# XTXBoard_2CPU.net
KiCad netlist of a schematic drawn in Altium Designer
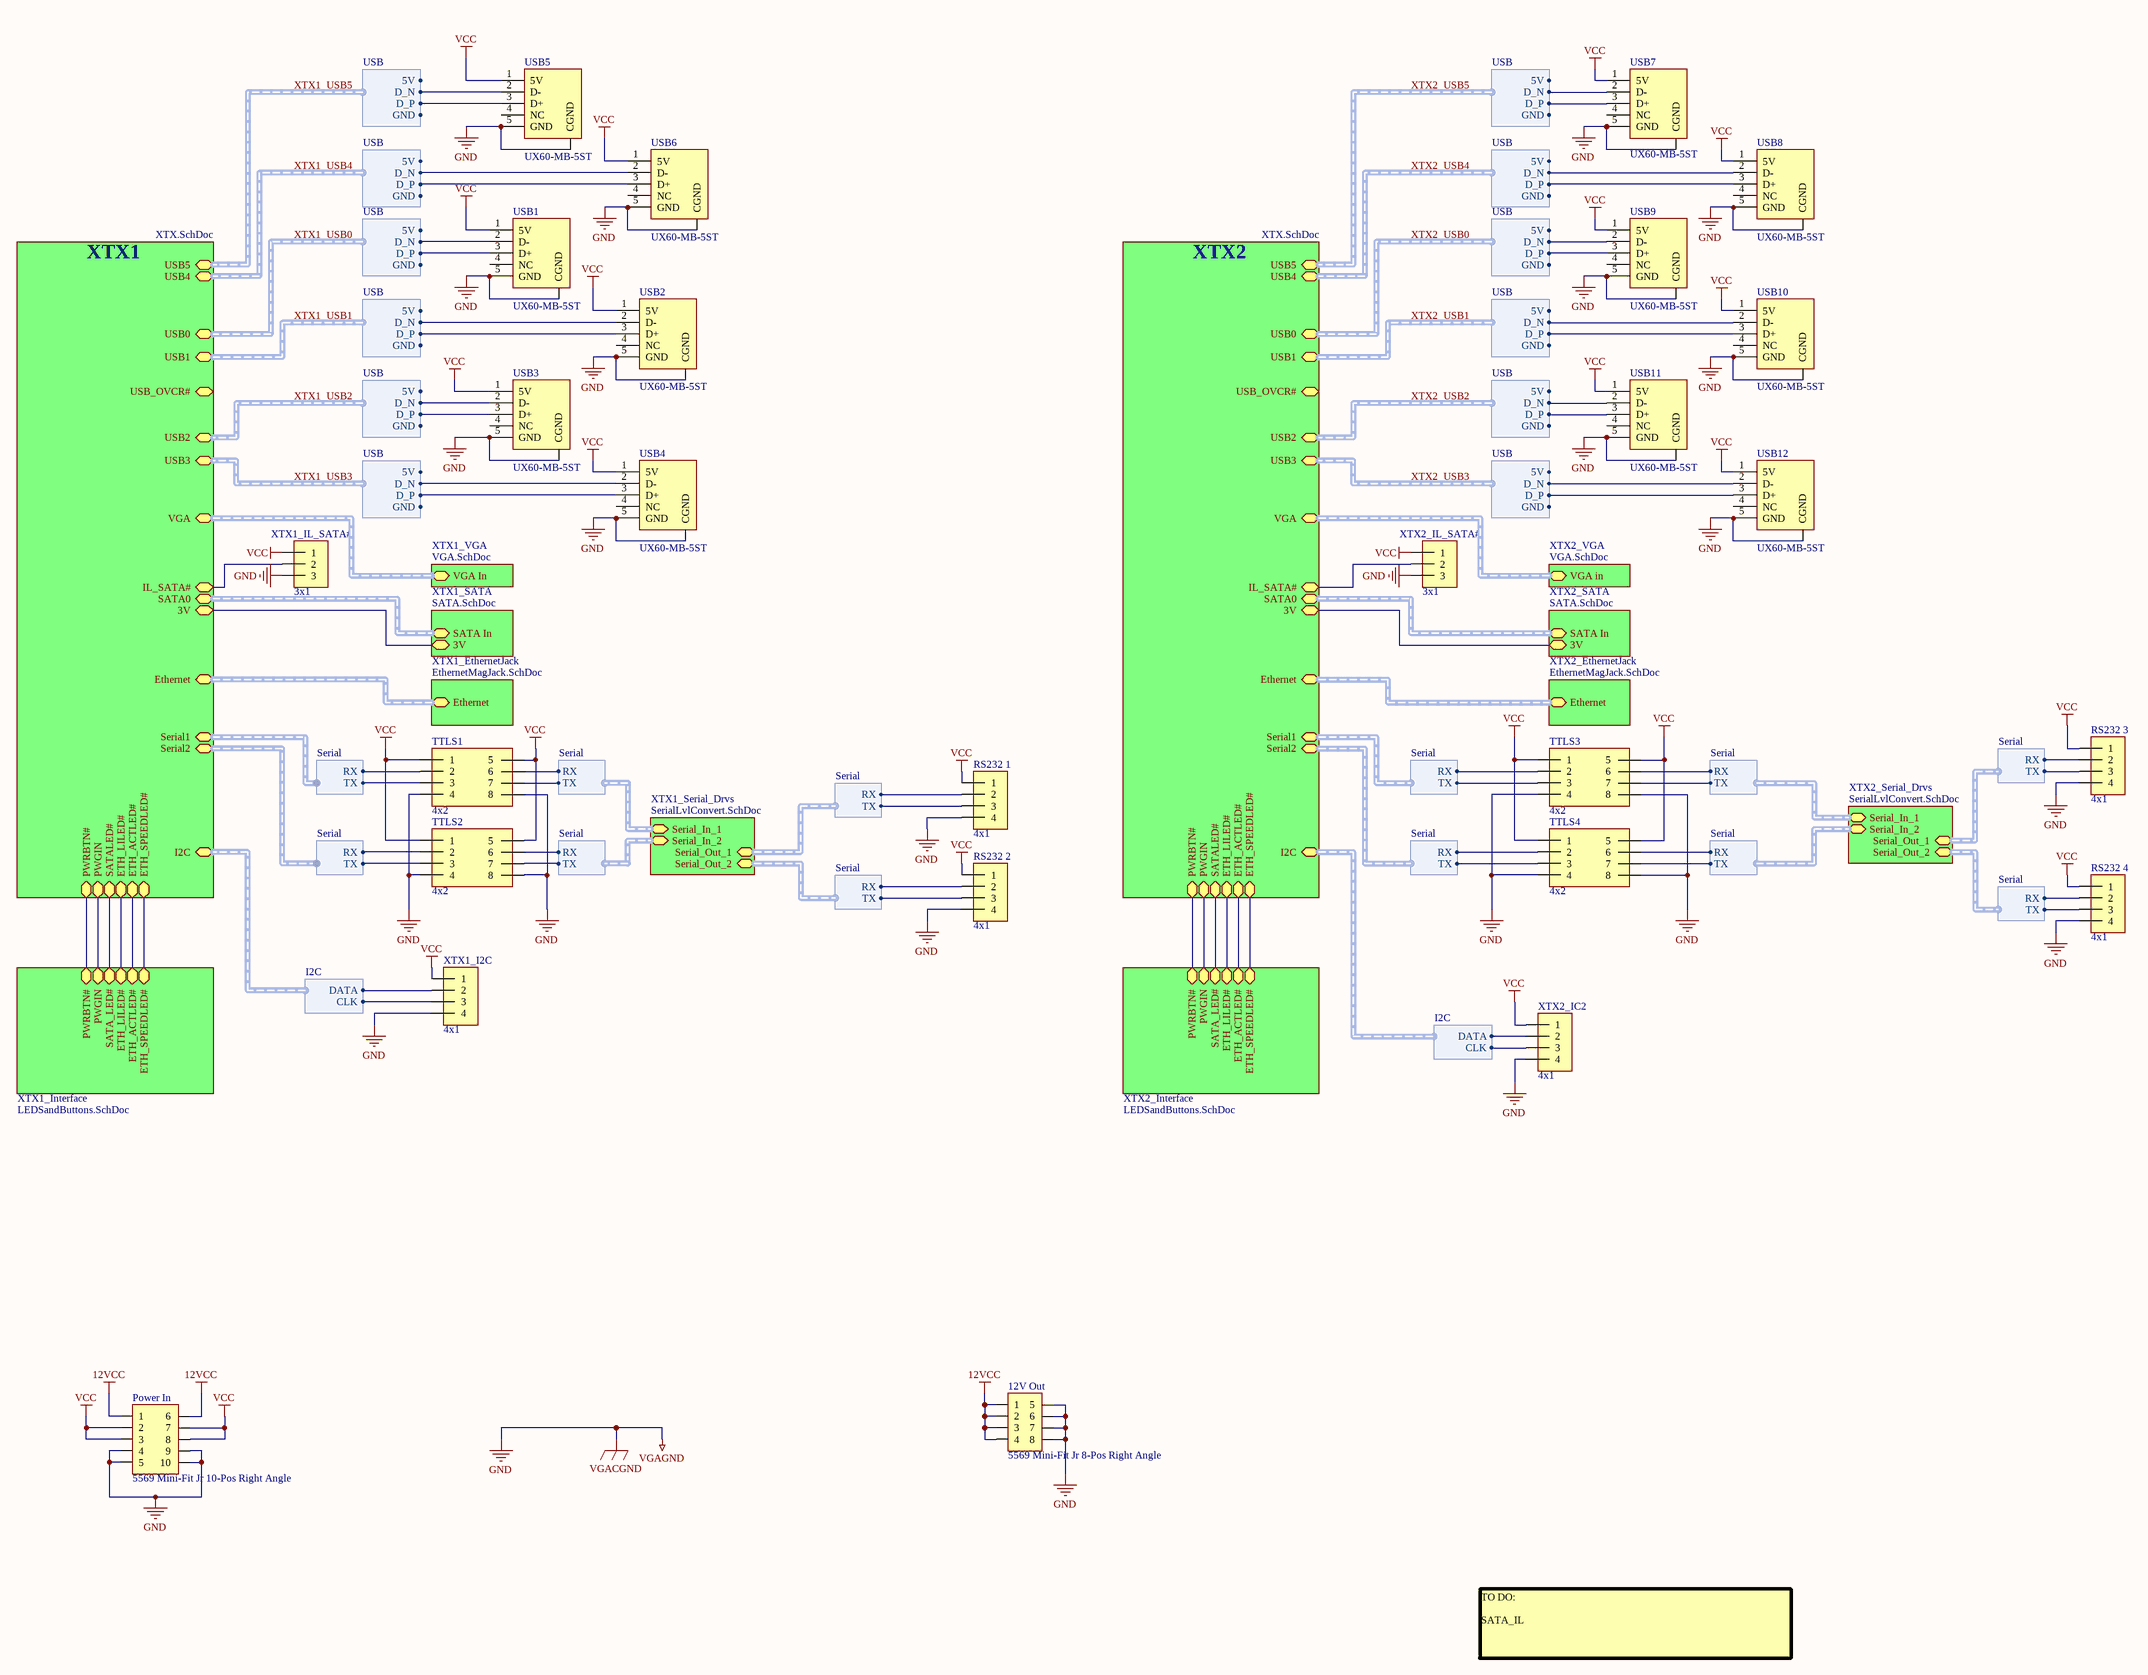
[diagram p0: XTXBoard(2CPU).SchDoc]

(export (version "E")
  (design (tool "Eeschema 10.0.6"))
  (components
    (comp (ref "12V Out")
      (value "5569 Mini-Fit Jr 8-Pos Right Angle")
      (footprint "MolexConnectors:8-POS 5569 Mini-Fit Jr 2")
      (libsource (lib "Molex") (part "5569 Mini-Fit Jr 8-Pos Right Angle"))
    )
    (comp (ref "Power In")
      (value "5569 Mini-Fit Jr 10-Pos Right Angle")
      (footprint "MolexConnectors:10-Pos 5569 Mini-Fit Jr 2")
      (libsource (lib "Molex") (part "5569 Mini-Fit Jr 10-Pos Right Angle"))
    )
    (comp (ref "RS232 1")
      (value "4x1")
      (footprint "Headers:Male 4x1")
      (description "4x1 100mil Header")
      (libsource (lib "Headers") (part "4x1"))
    )
    (comp (ref "RS232 2")
      (value "4x1")
      (footprint "Headers:Male 4x1")
      (description "4x1 100mil Header")
      (libsource (lib "Headers") (part "4x1"))
    )
    (comp (ref "RS232 3")
      (value "4x1")
      (footprint "Headers:Male 4x1")
      (description "4x1 100mil Header")
      (libsource (lib "Headers") (part "4x1"))
    )
    (comp (ref "RS232 4")
      (value "4x1")
      (footprint "Headers:Male 4x1")
      (description "4x1 100mil Header")
      (libsource (lib "Headers") (part "4x1"))
    )
    (comp (ref "TTLS1")
      (value "4x2")
      (footprint "Headers:Male 4x2")
      (description "4x2 100mil Header")
      (libsource (lib "Headers") (part "4x2"))
    )
    (comp (ref "TTLS2")
      (value "4x2")
      (footprint "Headers:Male 4x2")
      (description "4x2 100mil Header")
      (libsource (lib "Headers") (part "4x2"))
    )
    (comp (ref "TTLS3")
      (value "4x2")
      (footprint "Headers:FEMALE 4x2")
      (description "4x2 100mil Header")
      (libsource (lib "Headers") (part "4x2"))
    )
    (comp (ref "TTLS4")
      (value "4x2")
      (footprint "Headers:FEMALE 4x2")
      (description "4x2 100mil Header")
      (libsource (lib "Headers") (part "4x2"))
    )
    (comp (ref "USB1")
      (value "UX60-MB-5ST")
      (footprint "Hirose:UX60-MB-5ST")
      (description "miniUSB Type B SMT Connector")
      (libsource (lib "Hirose") (part "UX60-MB-5ST"))
    )
    (comp (ref "USB2")
      (value "UX60-MB-5ST")
      (footprint "Hirose:UX60-MB-5ST")
      (description "miniUSB Type B SMT Connector")
      (libsource (lib "Hirose") (part "UX60-MB-5ST"))
    )
    (comp (ref "USB3")
      (value "UX60-MB-5ST")
      (footprint "Hirose:UX60-MB-5ST")
      (description "miniUSB Type B SMT Connector")
      (libsource (lib "Hirose") (part "UX60-MB-5ST"))
    )
    (comp (ref "USB4")
      (value "UX60-MB-5ST")
      (footprint "Hirose:UX60-MB-5ST")
      (description "miniUSB Type B SMT Connector")
      (libsource (lib "Hirose") (part "UX60-MB-5ST"))
    )
    (comp (ref "USB5")
      (value "UX60-MB-5ST")
      (footprint "Hirose:UX60-MB-5ST")
      (description "miniUSB Type B SMT Connector")
      (libsource (lib "Hirose") (part "UX60-MB-5ST"))
    )
    (comp (ref "USB6")
      (value "UX60-MB-5ST")
      (footprint "Hirose:UX60-MB-5ST")
      (description "miniUSB Type B SMT Connector")
      (libsource (lib "Hirose") (part "UX60-MB-5ST"))
    )
    (comp (ref "USB7")
      (value "UX60-MB-5ST")
      (footprint "Hirose:UX60-MB-5ST")
      (description "miniUSB Type B SMT Connector")
      (libsource (lib "Hirose") (part "UX60-MB-5ST"))
    )
    (comp (ref "USB8")
      (value "UX60-MB-5ST")
      (footprint "Hirose:UX60-MB-5ST")
      (description "miniUSB Type B SMT Connector")
      (libsource (lib "Hirose") (part "UX60-MB-5ST"))
    )
    (comp (ref "USB9")
      (value "UX60-MB-5ST")
      (footprint "Hirose:UX60-MB-5ST")
      (description "miniUSB Type B SMT Connector")
      (libsource (lib "Hirose") (part "UX60-MB-5ST"))
    )
    (comp (ref "USB10")
      (value "UX60-MB-5ST")
      (footprint "Hirose:UX60-MB-5ST")
      (description "miniUSB Type B SMT Connector")
      (libsource (lib "Hirose") (part "UX60-MB-5ST"))
    )
    (comp (ref "USB11")
      (value "UX60-MB-5ST")
      (footprint "Hirose:UX60-MB-5ST")
      (description "miniUSB Type B SMT Connector")
      (libsource (lib "Hirose") (part "UX60-MB-5ST"))
    )
    (comp (ref "USB12")
      (value "UX60-MB-5ST")
      (footprint "Hirose:UX60-MB-5ST")
      (description "miniUSB Type B SMT Connector")
      (libsource (lib "Hirose") (part "UX60-MB-5ST"))
    )
    (comp (ref "XTX1_I2C")
      (value "4x1")
      (footprint "Headers:Male 4x1")
      (description "4x1 100mil Header")
      (libsource (lib "Headers") (part "4x1"))
    )
    (comp (ref "XTX1_IL_SATA#")
      (value "3x1")
      (footprint "Headers:Male 3x1")
      (description "3x1 100mil Header")
      (libsource (lib "Headers") (part "3x1"))
    )
    (comp (ref "XTX2_IC2")
      (value "4x1")
      (footprint "Headers:Male 4x1")
      (description "4x1 100mil Header")
      (libsource (lib "Headers") (part "4x1"))
    )
    (comp (ref "XTX2_IL_SATA#")
      (value "3x1")
      (footprint "Headers:Male 3x1")
      (description "3x1 100mil Header")
      (libsource (lib "Headers") (part "3x1"))
    )
  )
  (nets
    (net (code "25") (name "/IL_SATA#") (class "Default")
      (node (ref "XTX2_IL_SATA#") (pin "2") (pinfunction "2_2") (pintype "passive"))
    )
    (net (code "26") (name "/IL_SATA#_1") (class "Default")
      (node (ref "XTX1_IL_SATA#") (pin "2") (pinfunction "2_2") (pintype "passive"))
    )
    (net (code "53") (name "12VCC") (class "Default")
      (node (ref "12V Out") (pin "1") (pinfunction "1_1") (pintype "passive"))
      (node (ref "12V Out") (pin "2") (pinfunction "2_2") (pintype "passive"))
      (node (ref "12V Out") (pin "3") (pinfunction "3_3") (pintype "passive"))
      (node (ref "12V Out") (pin "4") (pinfunction "4_4") (pintype "passive"))
      (node (ref "Power In") (pin "1") (pinfunction "1_1") (pintype "passive"))
      (node (ref "Power In") (pin "6") (pinfunction "6_6") (pintype "passive"))
    )
    (net (code "54") (name "GND") (class "Default")
      (node (ref "12V Out") (pin "5") (pinfunction "5_5") (pintype "passive"))
      (node (ref "12V Out") (pin "6") (pinfunction "6_6") (pintype "passive"))
      (node (ref "12V Out") (pin "7") (pinfunction "7_7") (pintype "passive"))
      (node (ref "12V Out") (pin "8") (pinfunction "8_8") (pintype "passive"))
      (node (ref "Power In") (pin "10") (pinfunction "10_10") (pintype "passive"))
      (node (ref "Power In") (pin "4") (pinfunction "4_4") (pintype "passive"))
      (node (ref "Power In") (pin "5") (pinfunction "5_5") (pintype "passive"))
      (node (ref "Power In") (pin "9") (pinfunction "9_9") (pintype "passive"))
      (node (ref "RS232 1") (pin "4") (pinfunction "4_4") (pintype "passive"))
      (node (ref "RS232 2") (pin "4") (pinfunction "4_4") (pintype "passive"))
      (node (ref "RS232 3") (pin "4") (pinfunction "4_4") (pintype "passive"))
      (node (ref "RS232 4") (pin "4") (pinfunction "4_4") (pintype "passive"))
      (node (ref "TTLS1") (pin "4") (pinfunction "4_4") (pintype "passive"))
      (node (ref "TTLS1") (pin "8") (pinfunction "8_8") (pintype "passive"))
      (node (ref "TTLS2") (pin "4") (pinfunction "4_4") (pintype "passive"))
      (node (ref "TTLS2") (pin "8") (pinfunction "8_8") (pintype "passive"))
      (node (ref "TTLS3") (pin "4") (pinfunction "4_4") (pintype "passive"))
      (node (ref "TTLS3") (pin "8") (pinfunction "8_8") (pintype "passive"))
      (node (ref "TTLS4") (pin "4") (pinfunction "4_4") (pintype "passive"))
      (node (ref "TTLS4") (pin "8") (pinfunction "8_8") (pintype "passive"))
      (node (ref "USB1") (pin "5") (pinfunction "GND_5") (pintype "passive"))
      (node (ref "USB1") (pin "CGND") (pinfunction "CGND_CGND") (pintype "passive"))
      (node (ref "USB10") (pin "5") (pinfunction "GND_5") (pintype "passive"))
      (node (ref "USB10") (pin "CGND") (pinfunction "CGND_CGND") (pintype "passive"))
      (node (ref "USB11") (pin "5") (pinfunction "GND_5") (pintype "passive"))
      (node (ref "USB11") (pin "CGND") (pinfunction "CGND_CGND") (pintype "passive"))
      (node (ref "USB12") (pin "5") (pinfunction "GND_5") (pintype "passive"))
      (node (ref "USB12") (pin "CGND") (pinfunction "CGND_CGND") (pintype "passive"))
      (node (ref "USB2") (pin "5") (pinfunction "GND_5") (pintype "passive"))
      (node (ref "USB2") (pin "CGND") (pinfunction "CGND_CGND") (pintype "passive"))
      (node (ref "USB3") (pin "5") (pinfunction "GND_5") (pintype "passive"))
      (node (ref "USB3") (pin "CGND") (pinfunction "CGND_CGND") (pintype "passive"))
      (node (ref "USB4") (pin "5") (pinfunction "GND_5") (pintype "passive"))
      (node (ref "USB4") (pin "CGND") (pinfunction "CGND_CGND") (pintype "passive"))
      (node (ref "USB5") (pin "5") (pinfunction "GND_5") (pintype "passive"))
      (node (ref "USB5") (pin "CGND") (pinfunction "CGND_CGND") (pintype "passive"))
      (node (ref "USB6") (pin "5") (pinfunction "GND_5") (pintype "passive"))
      (node (ref "USB6") (pin "CGND") (pinfunction "CGND_CGND") (pintype "passive"))
      (node (ref "USB7") (pin "5") (pinfunction "GND_5") (pintype "passive"))
      (node (ref "USB7") (pin "CGND") (pinfunction "CGND_CGND") (pintype "passive"))
      (node (ref "USB8") (pin "5") (pinfunction "GND_5") (pintype "passive"))
      (node (ref "USB8") (pin "CGND") (pinfunction "CGND_CGND") (pintype "passive"))
      (node (ref "USB9") (pin "5") (pinfunction "GND_5") (pintype "passive"))
      (node (ref "USB9") (pin "CGND") (pinfunction "CGND_CGND") (pintype "passive"))
      (node (ref "XTX1_I2C") (pin "4") (pinfunction "4_4") (pintype "passive"))
      (node (ref "XTX1_IL_SATA#") (pin "3") (pinfunction "3_3") (pintype "passive"))
      (node (ref "XTX2_IC2") (pin "4") (pinfunction "4_4") (pintype "passive"))
      (node (ref "XTX2_IL_SATA#") (pin "3") (pinfunction "3_3") (pintype "passive"))
    )
    (net (code "55") (name "VCC") (class "Default")
      (node (ref "Power In") (pin "2") (pinfunction "2_2") (pintype "passive"))
      (node (ref "Power In") (pin "3") (pinfunction "3_3") (pintype "passive"))
      (node (ref "Power In") (pin "7") (pinfunction "7_7") (pintype "passive"))
      (node (ref "Power In") (pin "8") (pinfunction "8_8") (pintype "passive"))
      (node (ref "RS232 1") (pin "1") (pinfunction "1_1") (pintype "passive"))
      (node (ref "RS232 2") (pin "1") (pinfunction "1_1") (pintype "passive"))
      (node (ref "RS232 3") (pin "1") (pinfunction "1_1") (pintype "passive"))
      (node (ref "RS232 4") (pin "1") (pinfunction "1_1") (pintype "passive"))
      (node (ref "TTLS1") (pin "1") (pinfunction "1_1") (pintype "passive"))
      (node (ref "TTLS1") (pin "5") (pinfunction "5_5") (pintype "passive"))
      (node (ref "TTLS2") (pin "1") (pinfunction "1_1") (pintype "passive"))
      (node (ref "TTLS2") (pin "5") (pinfunction "5_5") (pintype "passive"))
      (node (ref "TTLS3") (pin "1") (pinfunction "1_1") (pintype "passive"))
      (node (ref "TTLS3") (pin "5") (pinfunction "5_5") (pintype "passive"))
      (node (ref "TTLS4") (pin "1") (pinfunction "1_1") (pintype "passive"))
      (node (ref "TTLS4") (pin "5") (pinfunction "5_5") (pintype "passive"))
      (node (ref "USB1") (pin "1") (pinfunction "5V_1") (pintype "passive"))
      (node (ref "USB10") (pin "1") (pinfunction "5V_1") (pintype "passive"))
      (node (ref "USB11") (pin "1") (pinfunction "5V_1") (pintype "passive"))
      (node (ref "USB12") (pin "1") (pinfunction "5V_1") (pintype "passive"))
      (node (ref "USB2") (pin "1") (pinfunction "5V_1") (pintype "passive"))
      (node (ref "USB3") (pin "1") (pinfunction "5V_1") (pintype "passive"))
      (node (ref "USB4") (pin "1") (pinfunction "5V_1") (pintype "passive"))
      (node (ref "USB5") (pin "1") (pinfunction "5V_1") (pintype "passive"))
      (node (ref "USB6") (pin "1") (pinfunction "5V_1") (pintype "passive"))
      (node (ref "USB7") (pin "1") (pinfunction "5V_1") (pintype "passive"))
      (node (ref "USB8") (pin "1") (pinfunction "5V_1") (pintype "passive"))
      (node (ref "USB9") (pin "1") (pinfunction "5V_1") (pintype "passive"))
      (node (ref "XTX1_I2C") (pin "1") (pinfunction "1_1") (pintype "passive"))
      (node (ref "XTX1_IL_SATA#") (pin "1") (pinfunction "1_1") (pintype "passive"))
      (node (ref "XTX2_IC2") (pin "1") (pinfunction "1_1") (pintype "passive"))
      (node (ref "XTX2_IL_SATA#") (pin "1") (pinfunction "1_1") (pintype "passive"))
    )
    (net (code "56") (name "unconnected-(RS232 1-Pad2)") (class "Default")
      (node (ref "RS232 1") (pin "2") (pinfunction "2_2") (pintype "passive"))
    )
    (net (code "57") (name "unconnected-(RS232 1-Pad3)") (class "Default")
      (node (ref "RS232 1") (pin "3") (pinfunction "3_3") (pintype "passive"))
    )
    (net (code "58") (name "unconnected-(RS232 2-Pad2)") (class "Default")
      (node (ref "RS232 2") (pin "2") (pinfunction "2_2") (pintype "passive"))
    )
    (net (code "59") (name "unconnected-(RS232 2-Pad3)") (class "Default")
      (node (ref "RS232 2") (pin "3") (pinfunction "3_3") (pintype "passive"))
    )
    (net (code "60") (name "unconnected-(RS232 3-Pad2)") (class "Default")
      (node (ref "RS232 3") (pin "2") (pinfunction "2_2") (pintype "passive"))
    )
    (net (code "61") (name "unconnected-(RS232 3-Pad3)") (class "Default")
      (node (ref "RS232 3") (pin "3") (pinfunction "3_3") (pintype "passive"))
    )
    (net (code "62") (name "unconnected-(RS232 4-Pad2)") (class "Default")
      (node (ref "RS232 4") (pin "2") (pinfunction "2_2") (pintype "passive"))
    )
    (net (code "63") (name "unconnected-(RS232 4-Pad3)") (class "Default")
      (node (ref "RS232 4") (pin "3") (pinfunction "3_3") (pintype "passive"))
    )
    (net (code "64") (name "unconnected-(TTLS1-Pad2)") (class "Default")
      (node (ref "TTLS1") (pin "2") (pinfunction "2_2") (pintype "passive"))
    )
    (net (code "65") (name "unconnected-(TTLS1-Pad3)") (class "Default")
      (node (ref "TTLS1") (pin "3") (pinfunction "3_3") (pintype "passive"))
    )
    (net (code "66") (name "unconnected-(TTLS1-Pad6)") (class "Default")
      (node (ref "TTLS1") (pin "6") (pinfunction "6_6") (pintype "passive"))
    )
    (net (code "67") (name "unconnected-(TTLS1-Pad7)") (class "Default")
      (node (ref "TTLS1") (pin "7") (pinfunction "7_7") (pintype "passive"))
    )
    (net (code "68") (name "unconnected-(TTLS2-Pad2)") (class "Default")
      (node (ref "TTLS2") (pin "2") (pinfunction "2_2") (pintype "passive"))
    )
    (net (code "69") (name "unconnected-(TTLS2-Pad3)") (class "Default")
      (node (ref "TTLS2") (pin "3") (pinfunction "3_3") (pintype "passive"))
    )
    (net (code "70") (name "unconnected-(TTLS2-Pad6)") (class "Default")
      (node (ref "TTLS2") (pin "6") (pinfunction "6_6") (pintype "passive"))
    )
    (net (code "71") (name "unconnected-(TTLS2-Pad7)") (class "Default")
      (node (ref "TTLS2") (pin "7") (pinfunction "7_7") (pintype "passive"))
    )
    (net (code "72") (name "unconnected-(TTLS3-Pad2)") (class "Default")
      (node (ref "TTLS3") (pin "2") (pinfunction "2_2") (pintype "passive"))
    )
    (net (code "73") (name "unconnected-(TTLS3-Pad3)") (class "Default")
      (node (ref "TTLS3") (pin "3") (pinfunction "3_3") (pintype "passive"))
    )
    (net (code "74") (name "unconnected-(TTLS3-Pad6)") (class "Default")
      (node (ref "TTLS3") (pin "6") (pinfunction "6_6") (pintype "passive"))
    )
    (net (code "75") (name "unconnected-(TTLS3-Pad7)") (class "Default")
      (node (ref "TTLS3") (pin "7") (pinfunction "7_7") (pintype "passive"))
    )
    (net (code "76") (name "unconnected-(TTLS4-Pad2)") (class "Default")
      (node (ref "TTLS4") (pin "2") (pinfunction "2_2") (pintype "passive"))
    )
    (net (code "77") (name "unconnected-(TTLS4-Pad3)") (class "Default")
      (node (ref "TTLS4") (pin "3") (pinfunction "3_3") (pintype "passive"))
    )
    (net (code "78") (name "unconnected-(TTLS4-Pad6)") (class "Default")
      (node (ref "TTLS4") (pin "6") (pinfunction "6_6") (pintype "passive"))
    )
    (net (code "79") (name "unconnected-(TTLS4-Pad7)") (class "Default")
      (node (ref "TTLS4") (pin "7") (pinfunction "7_7") (pintype "passive"))
    )
    (net (code "80") (name "unconnected-(USB1-D+-Pad3)") (class "Default")
      (node (ref "USB1") (pin "3") (pinfunction "D+_3") (pintype "passive"))
    )
    (net (code "81") (name "unconnected-(USB1-D--Pad2)") (class "Default")
      (node (ref "USB1") (pin "2") (pinfunction "D-_2") (pintype "passive"))
    )
    (net (code "82") (name "unconnected-(USB1-NC-Pad4)") (class "Default")
      (node (ref "USB1") (pin "4") (pinfunction "NC_4") (pintype "passive"))
    )
    (net (code "83") (name "unconnected-(USB2-D+-Pad3)") (class "Default")
      (node (ref "USB2") (pin "3") (pinfunction "D+_3") (pintype "passive"))
    )
    (net (code "84") (name "unconnected-(USB2-D--Pad2)") (class "Default")
      (node (ref "USB2") (pin "2") (pinfunction "D-_2") (pintype "passive"))
    )
    (net (code "85") (name "unconnected-(USB2-NC-Pad4)") (class "Default")
      (node (ref "USB2") (pin "4") (pinfunction "NC_4") (pintype "passive"))
    )
    (net (code "86") (name "unconnected-(USB3-D+-Pad3)") (class "Default")
      (node (ref "USB3") (pin "3") (pinfunction "D+_3") (pintype "passive"))
    )
    (net (code "87") (name "unconnected-(USB3-D--Pad2)") (class "Default")
      (node (ref "USB3") (pin "2") (pinfunction "D-_2") (pintype "passive"))
    )
    (net (code "88") (name "unconnected-(USB3-NC-Pad4)") (class "Default")
      (node (ref "USB3") (pin "4") (pinfunction "NC_4") (pintype "passive"))
    )
    (net (code "89") (name "unconnected-(USB4-D+-Pad3)") (class "Default")
      (node (ref "USB4") (pin "3") (pinfunction "D+_3") (pintype "passive"))
    )
    (net (code "90") (name "unconnected-(USB4-D--Pad2)") (class "Default")
      (node (ref "USB4") (pin "2") (pinfunction "D-_2") (pintype "passive"))
    )
    (net (code "91") (name "unconnected-(USB4-NC-Pad4)") (class "Default")
      (node (ref "USB4") (pin "4") (pinfunction "NC_4") (pintype "passive"))
    )
    (net (code "92") (name "unconnected-(USB5-D+-Pad3)") (class "Default")
      (node (ref "USB5") (pin "3") (pinfunction "D+_3") (pintype "passive"))
    )
    (net (code "93") (name "unconnected-(USB5-D--Pad2)") (class "Default")
      (node (ref "USB5") (pin "2") (pinfunction "D-_2") (pintype "passive"))
    )
    (net (code "94") (name "unconnected-(USB5-NC-Pad4)") (class "Default")
      (node (ref "USB5") (pin "4") (pinfunction "NC_4") (pintype "passive"))
    )
    (net (code "95") (name "unconnected-(USB6-D+-Pad3)") (class "Default")
      (node (ref "USB6") (pin "3") (pinfunction "D+_3") (pintype "passive"))
    )
    (net (code "96") (name "unconnected-(USB6-D--Pad2)") (class "Default")
      (node (ref "USB6") (pin "2") (pinfunction "D-_2") (pintype "passive"))
    )
    (net (code "97") (name "unconnected-(USB6-NC-Pad4)") (class "Default")
      (node (ref "USB6") (pin "4") (pinfunction "NC_4") (pintype "passive"))
    )
    (net (code "98") (name "unconnected-(USB7-D+-Pad3)") (class "Default")
      (node (ref "USB7") (pin "3") (pinfunction "D+_3") (pintype "passive"))
    )
    (net (code "99") (name "unconnected-(USB7-D--Pad2)") (class "Default")
      (node (ref "USB7") (pin "2") (pinfunction "D-_2") (pintype "passive"))
    )
    (net (code "100") (name "unconnected-(USB7-NC-Pad4)") (class "Default")
      (node (ref "USB7") (pin "4") (pinfunction "NC_4") (pintype "passive"))
    )
    (net (code "101") (name "unconnected-(USB8-D+-Pad3)") (class "Default")
      (node (ref "USB8") (pin "3") (pinfunction "D+_3") (pintype "passive"))
    )
    (net (code "102") (name "unconnected-(USB8-D--Pad2)") (class "Default")
      (node (ref "USB8") (pin "2") (pinfunction "D-_2") (pintype "passive"))
    )
    (net (code "103") (name "unconnected-(USB8-NC-Pad4)") (class "Default")
      (node (ref "USB8") (pin "4") (pinfunction "NC_4") (pintype "passive"))
    )
    (net (code "104") (name "unconnected-(USB9-D+-Pad3)") (class "Default")
      (node (ref "USB9") (pin "3") (pinfunction "D+_3") (pintype "passive"))
    )
    (net (code "105") (name "unconnected-(USB9-D--Pad2)") (class "Default")
      (node (ref "USB9") (pin "2") (pinfunction "D-_2") (pintype "passive"))
    )
    (net (code "106") (name "unconnected-(USB9-NC-Pad4)") (class "Default")
      (node (ref "USB9") (pin "4") (pinfunction "NC_4") (pintype "passive"))
    )
    (net (code "107") (name "unconnected-(USB10-D+-Pad3)") (class "Default")
      (node (ref "USB10") (pin "3") (pinfunction "D+_3") (pintype "passive"))
    )
    (net (code "108") (name "unconnected-(USB10-D--Pad2)") (class "Default")
      (node (ref "USB10") (pin "2") (pinfunction "D-_2") (pintype "passive"))
    )
    (net (code "109") (name "unconnected-(USB10-NC-Pad4)") (class "Default")
      (node (ref "USB10") (pin "4") (pinfunction "NC_4") (pintype "passive"))
    )
    (net (code "110") (name "unconnected-(USB11-D+-Pad3)") (class "Default")
      (node (ref "USB11") (pin "3") (pinfunction "D+_3") (pintype "passive"))
    )
    (net (code "111") (name "unconnected-(USB11-D--Pad2)") (class "Default")
      (node (ref "USB11") (pin "2") (pinfunction "D-_2") (pintype "passive"))
    )
    (net (code "112") (name "unconnected-(USB11-NC-Pad4)") (class "Default")
      (node (ref "USB11") (pin "4") (pinfunction "NC_4") (pintype "passive"))
    )
    (net (code "113") (name "unconnected-(USB12-D+-Pad3)") (class "Default")
      (node (ref "USB12") (pin "3") (pinfunction "D+_3") (pintype "passive"))
    )
    (net (code "114") (name "unconnected-(USB12-D--Pad2)") (class "Default")
      (node (ref "USB12") (pin "2") (pinfunction "D-_2") (pintype "passive"))
    )
    (net (code "115") (name "unconnected-(USB12-NC-Pad4)") (class "Default")
      (node (ref "USB12") (pin "4") (pinfunction "NC_4") (pintype "passive"))
    )
    (net (code "116") (name "unconnected-(XTX1_I2C-Pad2)") (class "Default")
      (node (ref "XTX1_I2C") (pin "2") (pinfunction "2_2") (pintype "passive"))
    )
    (net (code "117") (name "unconnected-(XTX1_I2C-Pad3)") (class "Default")
      (node (ref "XTX1_I2C") (pin "3") (pinfunction "3_3") (pintype "passive"))
    )
    (net (code "118") (name "unconnected-(XTX2_IC2-Pad2)") (class "Default")
      (node (ref "XTX2_IC2") (pin "2") (pinfunction "2_2") (pintype "passive"))
    )
    (net (code "119") (name "unconnected-(XTX2_IC2-Pad3)") (class "Default")
      (node (ref "XTX2_IC2") (pin "3") (pinfunction "3_3") (pintype "passive"))
    )
  )
)
